# Lipo-Charger-5V-setup_RevC.net
KiCad netlist of a schematic drawn in EAGLE
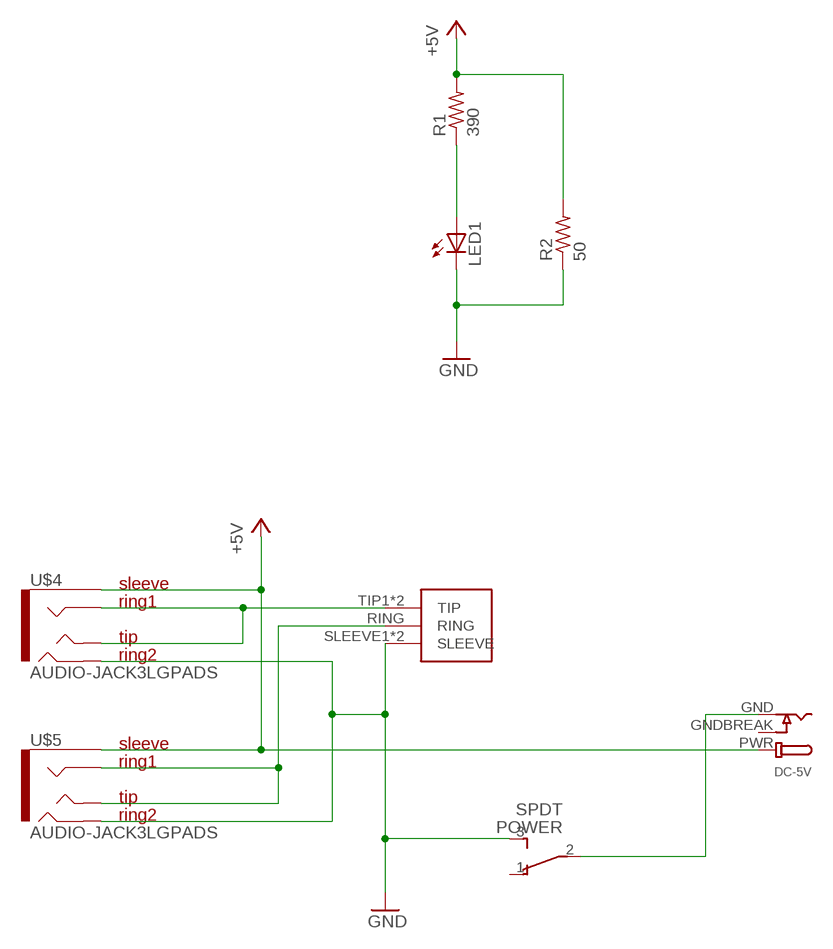
[diagram p0: schematic, sheet 1]

(export (version "E")
  (design (tool "Eeschema 10.0.6"))
  (components
    (comp (ref "AUDIO_OUT")
      (value "1/8\"-F-STEREO-PCB")
      (footprint "eagle-import:1_8_-F-STEREO-PCB")
      (libsource (lib "eagle-import") (part "1/8{dblquote}-F-STEREO-PCB"))
    )
    (comp (ref "DC-5V")
      (value "DCBARRELPTH")
      (footprint "eagle-import:DCJACK_2MM_PTH")
      (libsource (lib "eagle-import") (part "DCBARRELPTH"))
    )
    (comp (ref "LED1")
      (value "LED3MM")
      (footprint "eagle-import:LED3MM")
      (libsource (lib "eagle-import") (part "LED3MM"))
    )
    (comp (ref "POWER")
      (value "SPDT")
      (footprint "eagle-import:SWITCH_SPDT-TE-CONNECT")
      (libsource (lib "eagle-import") (part "SWITCH_SPDTTE-CONNECT"))
    )
    (comp (ref "R1")
      (value "390")
      (footprint "eagle-import:0204_7")
      (libsource (lib "eagle-import") (part "R-US_0204/7"))
    )
    (comp (ref "R2")
      (value "50")
      (footprint "eagle-import:0204_7")
      (libsource (lib "eagle-import") (part "R-US_0204/7"))
    )
    (comp (ref "U$4")
      (value "AUDIO-JACK3LGPADS")
      (footprint "eagle-import:AUDIO-JACK-TRRS-SMD")
      (libsource (lib "eagle-import") (part "AUDIO-JACK3LGPADS"))
    )
    (comp (ref "U$5")
      (value "AUDIO-JACK3LGPADS")
      (footprint "eagle-import:AUDIO-JACK-TRRS-SMD")
      (libsource (lib "eagle-import") (part "AUDIO-JACK3LGPADS"))
    )
  )
  (nets
    (net (code "1") (name "+5V") (class "Default")
      (node (ref "DC-5V") (pin "PWR") (pinfunction "PWR_PWR") (pintype "power_in"))
      (node (ref "R1") (pin "2") (pinfunction "2_2") (pintype "passive"))
      (node (ref "R2") (pin "2") (pinfunction "2_2") (pintype "passive"))
      (node (ref "U$4") (pin "EARTH") (pinfunction "EARTH_EARTH") (pintype "bidirectional"))
      (node (ref "U$5") (pin "EARTH") (pinfunction "EARTH_EARTH") (pintype "bidirectional"))
    )
    (net (code "2") (name "/GNDBREAK") (class "Default")
      (node (ref "DC-5V") (pin "GNDBREAK") (pinfunction "GNDBREAK_GNDBREAK") (pintype "power_in"))
    )
    (net (code "3") (name "GND") (class "Default")
      (node (ref "AUDIO_OUT") (pin "SLEEVE1") (pinfunction "SLEEVE_SLEEVE1") (pintype "bidirectional"))
      (node (ref "AUDIO_OUT") (pin "SLEEVE2") (pinfunction "SLEEVE_SLEEVE2") (pintype "bidirectional"))
      (node (ref "LED1") (pin "K") (pinfunction "C_K") (pintype "passive"))
      (node (ref "POWER") (pin "3") (pinfunction "3_3") (pintype "passive"))
      (node (ref "R2") (pin "1") (pinfunction "1_1") (pintype "passive"))
      (node (ref "U$4") (pin "RING2") (pinfunction "RING2_RING2") (pintype "bidirectional"))
      (node (ref "U$5") (pin "RING2") (pinfunction "RING2_RING2") (pintype "bidirectional"))
    )
    (net (code "4") (name "Net-(AUDIO_OUT-PadRING)") (class "Default")
      (node (ref "AUDIO_OUT") (pin "RING") (pinfunction "RING_RING") (pintype "bidirectional"))
      (node (ref "U$5") (pin "RING1") (pinfunction "RING1_RING1") (pintype "bidirectional"))
      (node (ref "U$5") (pin "TIP") (pinfunction "TIP_TIP") (pintype "bidirectional"))
    )
    (net (code "5") (name "Net-(AUDIO_OUT-TIP-PadTIP1)") (class "Default")
      (node (ref "AUDIO_OUT") (pin "TIP1") (pinfunction "TIP_TIP1") (pintype "bidirectional"))
      (node (ref "AUDIO_OUT") (pin "TIP2") (pinfunction "TIP_TIP2") (pintype "bidirectional"))
      (node (ref "U$4") (pin "RING1") (pinfunction "RING1_RING1") (pintype "bidirectional"))
      (node (ref "U$4") (pin "TIP") (pinfunction "TIP_TIP") (pintype "bidirectional"))
    )
    (net (code "6") (name "Net-(DC-5V-PadGND)") (class "Default")
      (node (ref "DC-5V") (pin "GND") (pinfunction "GND_GND") (pintype "power_in"))
      (node (ref "POWER") (pin "2") (pinfunction "2_2") (pintype "passive"))
    )
    (net (code "7") (name "Net-(LED1-PadA)") (class "Default")
      (node (ref "LED1") (pin "A") (pinfunction "A_A") (pintype "passive"))
      (node (ref "R1") (pin "1") (pinfunction "1_1") (pintype "passive"))
    )
    (net (code "8") (name "unconnected-(POWER-Pad1)") (class "Default")
      (node (ref "POWER") (pin "1") (pinfunction "1_1") (pintype "passive"))
    )
  )
)
